# GPIO_Button_Grove_MOSFET_LED_R1_1.net
KiCad netlist of a schematic drawn in EasyEDA
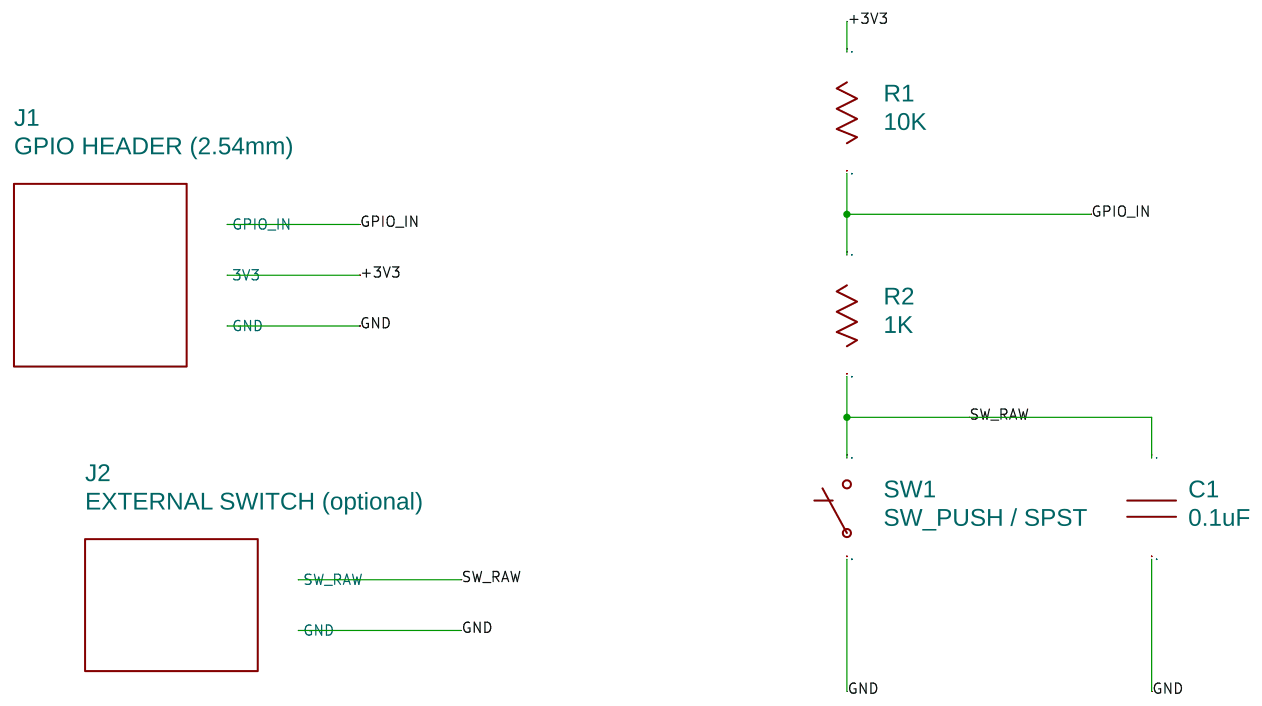
[diagram p0: GPIO_Push-Button_or_Switch_Input]
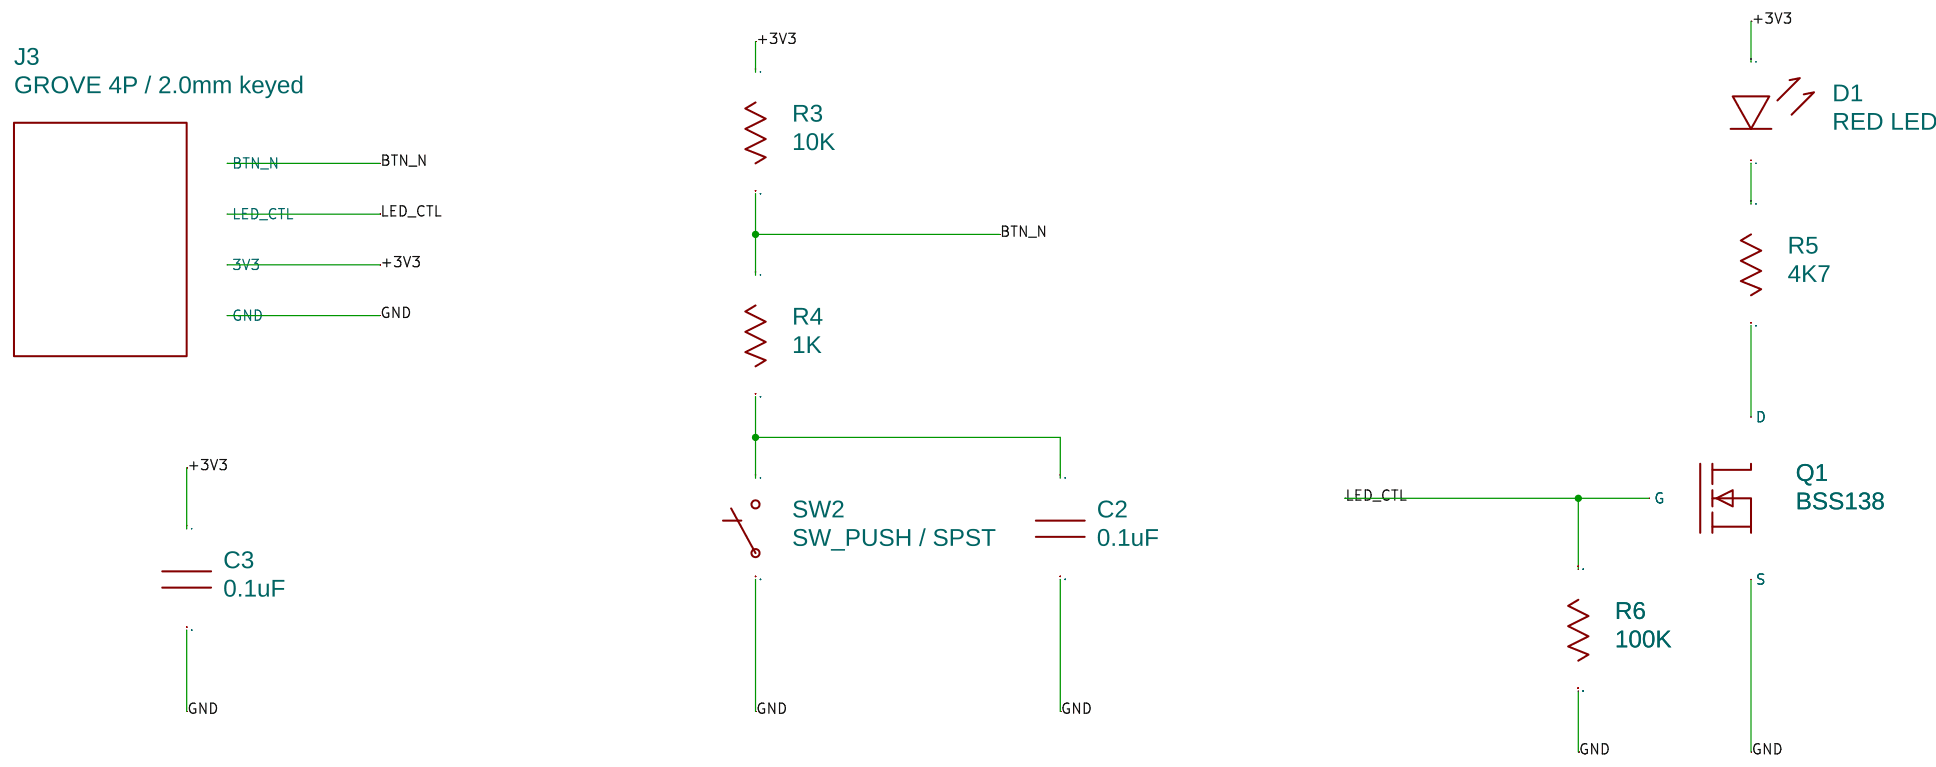
[diagram p1: GROVE_4P_Button_MOSFET_LED]

(export (version "E")
  (design (tool "Eeschema 10.0.6"))
  (components
    (comp (ref "C1") (value "0.1uF") (libsource (lib "") (part "0.1uF")))
    (comp (ref "J1") (value "GPIO HEADER (2.54mm)") (libsource (lib "") (part "GPIO HEADER (2.54mm)")))
    (comp (ref "J2")
      (value "EXTERNAL SWITCH (optional)")
      (libsource (lib "") (part "EXTERNAL SWITCH (optional)"))
    )
    (comp (ref "R1") (value "10K") (libsource (lib "") (part "10K")))
    (comp (ref "R2") (value "1K") (libsource (lib "") (part "1K")))
    (comp (ref "SW1") (value "SW_PUSH / SPST") (libsource (lib "") (part "SW_PUSH / SPST")))
    (comp (ref "C2") (value "0.1uF") (libsource (lib "") (part "0.1uF")))
    (comp (ref "C3") (value "0.1uF") (libsource (lib "") (part "0.1uF")))
    (comp (ref "D1") (value "RED LED") (libsource (lib "") (part "RED LED")))
    (comp (ref "J3") (value "GROVE 4P / 2.0mm keyed") (libsource (lib "") (part "GROVE 4P / 2.0mm keyed")))
    (comp (ref "Q1") (value "BSS138") (libsource (lib "") (part "BSS138")))
    (comp (ref "R3") (value "10K") (libsource (lib "") (part "10K")))
    (comp (ref "R4") (value "1K") (libsource (lib "") (part "1K")))
    (comp (ref "R5") (value "4K7") (libsource (lib "") (part "4K7")))
    (comp (ref "R6") (value "100K") (libsource (lib "") (part "100K")))
    (comp (ref "SW2") (value "SW_PUSH / SPST") (libsource (lib "") (part "SW_PUSH / SPST")))
  )
  (nets
    (net (code "1") (name "+3V3") (class "Default")
      (node (ref "C3") (pin "1") (pinfunction "1_1") (pintype "unspecified"))
      (node (ref "D1") (pin "2") (pinfunction "A_2") (pintype "unspecified"))
      (node (ref "J1") (pin "2") (pinfunction "3V3_2") (pintype "unspecified"))
      (node (ref "J3") (pin "3") (pinfunction "3V3_3") (pintype "unspecified"))
      (node (ref "R1") (pin "1") (pinfunction "1_1") (pintype "unspecified"))
      (node (ref "R3") (pin "1") (pinfunction "1_1") (pintype "unspecified"))
    )
    (net (code "2") (name "BTN_N") (class "Default")
      (node (ref "J3") (pin "1") (pinfunction "BTN_N_1") (pintype "unspecified"))
      (node (ref "R3") (pin "2") (pinfunction "2_2") (pintype "unspecified"))
      (node (ref "R4") (pin "1") (pinfunction "1_1") (pintype "unspecified"))
    )
    (net (code "3") (name "GND") (class "Default")
      (node (ref "C1") (pin "2") (pinfunction "2_2") (pintype "unspecified"))
      (node (ref "C2") (pin "2") (pinfunction "2_2") (pintype "unspecified"))
      (node (ref "C3") (pin "2") (pinfunction "2_2") (pintype "unspecified"))
      (node (ref "J1") (pin "3") (pinfunction "GND_3") (pintype "unspecified"))
      (node (ref "J2") (pin "2") (pinfunction "GND_2") (pintype "unspecified"))
      (node (ref "J3") (pin "4") (pinfunction "GND_4") (pintype "unspecified"))
      (node (ref "Q1") (pin "2") (pinfunction "S_2") (pintype "unspecified"))
      (node (ref "R6") (pin "2") (pinfunction "2_2") (pintype "unspecified"))
      (node (ref "SW1") (pin "3") (pinfunction "3_3") (pintype "unspecified"))
      (node (ref "SW2") (pin "3") (pinfunction "3_3") (pintype "unspecified"))
    )
    (net (code "4") (name "GPIO_IN") (class "Default")
      (node (ref "J1") (pin "1") (pinfunction "GPIO_IN_1") (pintype "unspecified"))
      (node (ref "R1") (pin "2") (pinfunction "2_2") (pintype "unspecified"))
      (node (ref "R2") (pin "1") (pinfunction "1_1") (pintype "unspecified"))
    )
    (net (code "5") (name "LED_CTL") (class "Default")
      (node (ref "J3") (pin "2") (pinfunction "LED_CTL_2") (pintype "unspecified"))
      (node (ref "Q1") (pin "1") (pinfunction "G_1") (pintype "unspecified"))
      (node (ref "R6") (pin "1") (pinfunction "1_1") (pintype "unspecified"))
    )
    (net (code "6") (name "Net-(C2-Pad1)") (class "Default")
      (node (ref "C2") (pin "1") (pinfunction "1_1") (pintype "unspecified"))
      (node (ref "R4") (pin "2") (pinfunction "2_2") (pintype "unspecified"))
      (node (ref "SW2") (pin "1") (pinfunction "1_1") (pintype "unspecified"))
    )
    (net (code "7") (name "Net-(D1-K)") (class "Default")
      (node (ref "D1") (pin "1") (pinfunction "K_1") (pintype "unspecified"))
      (node (ref "R5") (pin "1") (pinfunction "1_1") (pintype "unspecified"))
    )
    (net (code "8") (name "Net-(Q1-D)") (class "Default")
      (node (ref "Q1") (pin "3") (pinfunction "D_3") (pintype "unspecified"))
      (node (ref "R5") (pin "2") (pinfunction "2_2") (pintype "unspecified"))
    )
    (net (code "9") (name "SW_RAW") (class "Default")
      (node (ref "C1") (pin "1") (pinfunction "1_1") (pintype "unspecified"))
      (node (ref "J2") (pin "1") (pinfunction "SW_RAW_1") (pintype "unspecified"))
      (node (ref "R2") (pin "2") (pinfunction "2_2") (pintype "unspecified"))
      (node (ref "SW1") (pin "1") (pinfunction "1_1") (pintype "unspecified"))
    )
  )
)
